# DigitalInputs.net
KiCad netlist of a schematic drawn in Altium Designer
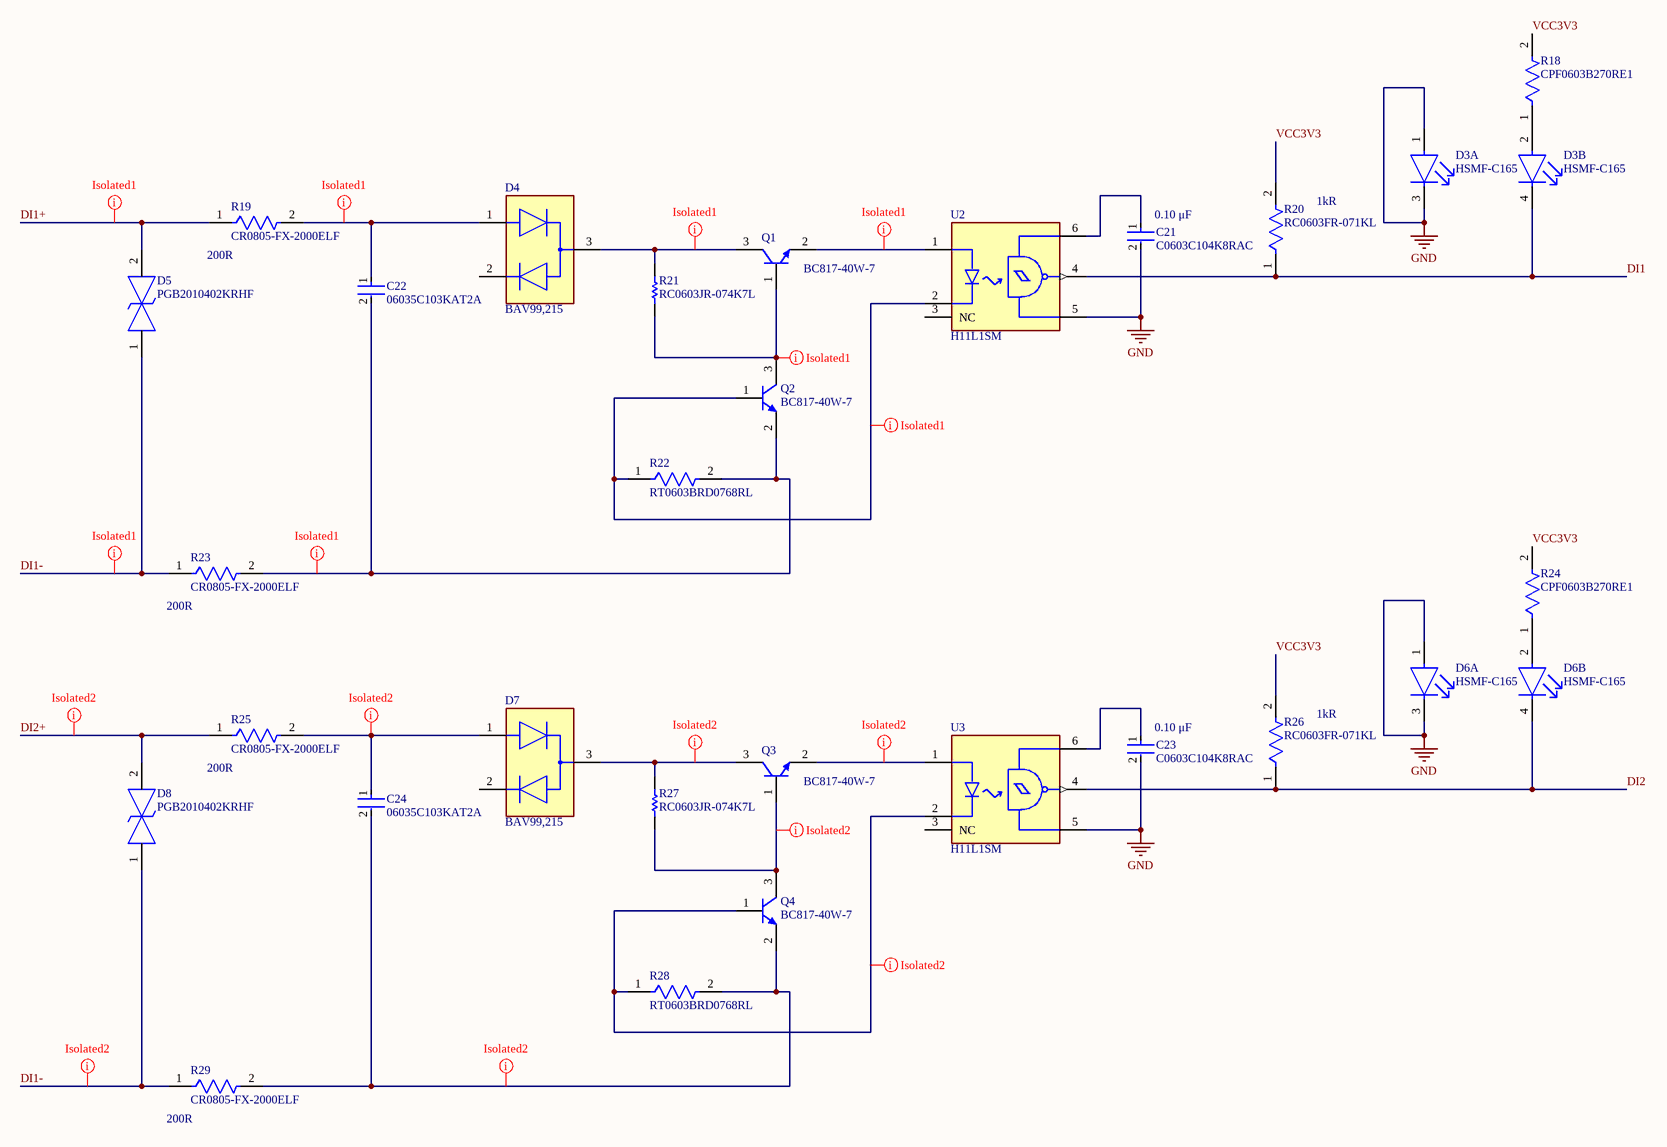
[diagram p0: DigitalInputs.SchDoc]

(export (version "E")
  (design (tool "Eeschema 10.0.6"))
  (components
    (comp (ref "C21")
      (value "C0603C104K8RAC")
      (footprint "FP-C0603C-CF-MFG")
      (description "C0603 0.10 μF X7R 30ppm/°C 10.00% 10 V")
      (fields
        (field (name "MANUFACTURER") "KEMET")
        (field (name "CAPACITANCE") "0.10 μF")
        (field (name "OCTOPART") "https://octopart.com/c0603c104k8rac-kemet-1325403")
      )
      (libsource (lib "Altium Content Vault") (part "b4654b650e69147ec39a6b967a45e02"))
    )
    (comp (ref "C22")
      (value "06035C103KAT2A")
      (footprint "FP-0603-L_1_6_0_15-W_0_81-MFG")
      (description "General Purpose Ceramic Capacitor, 0603, 10nF, 10%, X7R, 15%, 50V")
      (fields (field (name "VOLTAGE") "50V") (field (name "TOLERANCE") "10%"))
      (libsource (lib "Altium Content Vault") (part "02cd4be3c70576c341d710602a673aa"))
    )
    (comp (ref "C23")
      (value "C0603C104K8RAC")
      (footprint "FP-C0603C-CF-MFG")
      (description "C0603 0.10 μF X7R 30ppm/°C 10.00% 10 V")
      (fields
        (field (name "MANUFACTURER") "KEMET")
        (field (name "CAPACITANCE") "0.10 μF")
        (field (name "OCTOPART") "https://octopart.com/c0603c104k8rac-kemet-1325403")
      )
      (libsource (lib "Altium Content Vault") (part "b4654b650e69147ec39a6b967a45e02"))
    )
    (comp (ref "C24")
      (value "06035C103KAT2A")
      (footprint "FP-0603-L_1_6_0_15-W_0_81-MFG")
      (description "General Purpose Ceramic Capacitor, 0603, 10nF, 10%, X7R, 15%, 50V")
      (fields (field (name "VOLTAGE") "50V") (field (name "TOLERANCE") "10%"))
      (libsource (lib "Altium Content Vault") (part "02cd4be3c70576c341d710602a673aa"))
    )
    (comp (ref "D3")
      (value "HSMF-C165")
      (footprint "FP-HSMF-C165-MFG")
      (description "LED GREEN/RED DIFFUSED 0603 SMD")
      (libsource (lib "Altium Content Vault") (part "7c1fe340d8ce6b5db8c50b7ec3493de"))
    )
    (comp (ref "D4")
      (value "BAV99,215")
      (footprint "FP-SOT23-MFG")
      (description "DIODE ARRAY GP 100V 215MA SOT23")
      (libsource (lib "Altium Content Vault") (part "86a7eb6839269cc1691df5cbdd99f75"))
    )
    (comp (ref "D5")
      (value "PGB2010402KRHF")
      (footprint "DIONC1005X38N")
      (description "Littelfuse PGB2 Series Metal Oxide Varistor 0.07pF, Clamping 40V 0402 (1005M) Case")
      (fields (field (name "MOUSER PART NUMBER") "576-PGB2010402KRHF"))
      (libsource (lib "Schlib2") (part "PGB2010402KRHF"))
    )
    (comp (ref "D6")
      (value "HSMF-C165")
      (footprint "FP-HSMF-C165-MFG")
      (description "LED GREEN/RED DIFFUSED 0603 SMD")
      (libsource (lib "Altium Content Vault") (part "7c1fe340d8ce6b5db8c50b7ec3493de"))
    )
    (comp (ref "D7")
      (value "BAV99,215")
      (footprint "FP-SOT23-MFG")
      (description "DIODE ARRAY GP 100V 215MA SOT23")
      (libsource (lib "Altium Content Vault") (part "86a7eb6839269cc1691df5cbdd99f75"))
    )
    (comp (ref "D8")
      (value "PGB2010402KRHF")
      (footprint "DIONC1005X38N")
      (description "Littelfuse PGB2 Series Metal Oxide Varistor 0.07pF, Clamping 40V 0402 (1005M) Case")
      (fields (field (name "MOUSER PART NUMBER") "576-PGB2010402KRHF"))
      (libsource (lib "Schlib2") (part "PGB2010402KRHF"))
    )
    (comp (ref "Q1")
      (value "BC817-40W-7")
      (footprint "DIOD-SOT323-3_V")
      (description "NPN Small Signal Transistor, 45 V, 500 mA, -65 to 150 degC, 3-Pin SOT323, RoHS, Tape and Reel")
      (fields (field (name "MANUFACTURER") "DiodesIncorporated"))
      (libsource (lib "Altium Content Vault") (part "BJT-NPN-BEC-3"))
    )
    (comp (ref "Q2")
      (value "BC817-40W-7")
      (footprint "DIOD-SOT323-3_V")
      (description "NPN Small Signal Transistor, 45 V, 500 mA, -65 to 150 degC, 3-Pin SOT323, RoHS, Tape and Reel")
      (fields (field (name "MANUFACTURER") "DiodesIncorporated"))
      (libsource (lib "Altium Content Vault") (part "BJT-NPN-BEC-3"))
    )
    (comp (ref "Q3")
      (value "BC817-40W-7")
      (footprint "DIOD-SOT323-3_V")
      (description "NPN Small Signal Transistor, 45 V, 500 mA, -65 to 150 degC, 3-Pin SOT323, RoHS, Tape and Reel")
      (fields (field (name "MANUFACTURER") "DiodesIncorporated"))
      (libsource (lib "Altium Content Vault") (part "BJT-NPN-BEC-3"))
    )
    (comp (ref "Q4")
      (value "BC817-40W-7")
      (footprint "DIOD-SOT323-3_V")
      (description "NPN Small Signal Transistor, 45 V, 500 mA, -65 to 150 degC, 3-Pin SOT323, RoHS, Tape and Reel")
      (fields (field (name "MANUFACTURER") "DiodesIncorporated"))
      (libsource (lib "Altium Content Vault") (part "BJT-NPN-BEC-3"))
    )
    (comp (ref "R18")
      (value "CPF0603B270RE1")
      (footprint "FP-CPF0603-MFG")
      (description "RES SMD 270Ω 0.1% 1/16W 0603")
      (fields (field (name "TOLERANCE") "0.1%") (field (name "MANUFACTURER") "TE Connectivity"))
      (libsource (lib "Altium Content Vault") (part "1029c3af85768c4190bb7ad29bc67b5"))
    )
    (comp (ref "R19")
      (value "CR0805-FX-2000ELF")
      (footprint "FP-CR0805-IPC_B")
      (description "Thick Film Chip Resistors 0805 200Ω 0.125W 1% 100ppm/°C")
      (fields (field (name "TOLERANCE") "1%") (field (name "RESISTANCE") "200R"))
      (libsource (lib "Altium Content Vault") (part "1029c3af85768c4190bb7ad29bc67b5"))
    )
    (comp (ref "R20")
      (value "RC0603FR-071KL")
      (footprint "FP-RC0603-0_55-IPC_C")
      (description "RES 1K OHM 1% 1/10W 0603")
      (fields (field (name "RESISTANCE") "1kR") (field (name "TOLERANCE") "1%"))
      (libsource (lib "Altium Content Vault") (part "1029c3af85768c4190bb7ad29bc67b5"))
    )
    (comp (ref "R21")
      (value "RC0603JR-074K7L")
      (footprint "RESC1608X55X25ML10T15")
      (description "Chip Resistor, 4.7 KOhm, +/- 5%, 100 mW, -55 to 155 degC, 0603 (1608 Metric), RoHS, Tape and Reel")
      (fields (field (name "TOLERANCE") "5%") (field (name "MANUFACTURER") "Yageo"))
      (libsource (lib "Altium Content Vault") (part "RES-2"))
    )
    (comp (ref "R22")
      (value "RT0603BRD0768RL")
      (footprint "FP-RT0603-MFG")
      (description "RES 68.0 OHM 1/10W .1% SMD 0603")
      (fields
        (field (name "MANUFACTURER") "Yageo")
        (field (name "OCTOPART") "https://octopart.com/rt0603brd0768rl-yageo-1442936")
      )
      (libsource (lib "Altium Content Vault") (part "1029c3af85768c4190bb7ad29bc67b5"))
    )
    (comp (ref "R23")
      (value "CR0805-FX-2000ELF")
      (footprint "FP-CR0805-IPC_B")
      (description "Thick Film Chip Resistors 0805 200Ω 0.125W 1% 100ppm/°C")
      (fields (field (name "TOLERANCE") "1%") (field (name "RESISTANCE") "200R"))
      (libsource (lib "Altium Content Vault") (part "1029c3af85768c4190bb7ad29bc67b5"))
    )
    (comp (ref "R24")
      (value "CPF0603B270RE1")
      (footprint "FP-CPF0603-MFG")
      (description "RES SMD 270Ω 0.1% 1/16W 0603")
      (fields (field (name "TOLERANCE") "0.1%") (field (name "MANUFACTURER") "TE Connectivity"))
      (libsource (lib "Altium Content Vault") (part "1029c3af85768c4190bb7ad29bc67b5"))
    )
    (comp (ref "R25")
      (value "CR0805-FX-2000ELF")
      (footprint "FP-CR0805-IPC_B")
      (description "Thick Film Chip Resistors 0805 200Ω 0.125W 1% 100ppm/°C")
      (fields (field (name "TOLERANCE") "1%") (field (name "RESISTANCE") "200R"))
      (libsource (lib "Altium Content Vault") (part "1029c3af85768c4190bb7ad29bc67b5"))
    )
    (comp (ref "R26")
      (value "RC0603FR-071KL")
      (footprint "FP-RC0603-0_55-IPC_C")
      (description "RES 1K OHM 1% 1/10W 0603")
      (fields (field (name "RESISTANCE") "1kR") (field (name "TOLERANCE") "1%"))
      (libsource (lib "Altium Content Vault") (part "1029c3af85768c4190bb7ad29bc67b5"))
    )
    (comp (ref "R27")
      (value "RC0603JR-074K7L")
      (footprint "RESC1608X55X25ML10T15")
      (description "Chip Resistor, 4.7 KOhm, +/- 5%, 100 mW, -55 to 155 degC, 0603 (1608 Metric), RoHS, Tape and Reel")
      (fields (field (name "TOLERANCE") "5%") (field (name "MANUFACTURER") "Yageo"))
      (libsource (lib "Altium Content Vault") (part "RES-2"))
    )
    (comp (ref "R28")
      (value "RT0603BRD0768RL")
      (footprint "FP-RT0603-MFG")
      (description "RES 68.0 OHM 1/10W .1% SMD 0603")
      (fields
        (field (name "MANUFACTURER") "Yageo")
        (field (name "OCTOPART") "https://octopart.com/rt0603brd0768rl-yageo-1442936")
      )
      (libsource (lib "Altium Content Vault") (part "1029c3af85768c4190bb7ad29bc67b5"))
    )
    (comp (ref "R29")
      (value "CR0805-FX-2000ELF")
      (footprint "FP-CR0805-IPC_B")
      (description "Thick Film Chip Resistors 0805 200Ω 0.125W 1% 100ppm/°C")
      (fields (field (name "TOLERANCE") "1%") (field (name "RESISTANCE") "200R"))
      (libsource (lib "Altium Content Vault") (part "1029c3af85768c4190bb7ad29bc67b5"))
    )
    (comp (ref "U2")
      (value "H11L1SM")
      (footprint "FP-646BY-MFG")
      (description "OPTOISO 4.17KV OPN COLL 6SMD")
      (fields
        (field (name "MANUFACTURER") "ON Semiconductor")
        (field (name "OCTOPART") "https://octopart.com/h11l1sm-on+semiconductor-84328916")
      )
      (libsource (lib "Altium Content Vault") (part "e3909e1d209c9787f54f3dc2cca47f5"))
    )
    (comp (ref "U3")
      (value "H11L1SM")
      (footprint "FP-646BY-MFG")
      (description "OPTOISO 4.17KV OPN COLL 6SMD")
      (fields
        (field (name "MANUFACTURER") "ON Semiconductor")
        (field (name "OCTOPART") "https://octopart.com/h11l1sm-on+semiconductor-84328916")
      )
      (libsource (lib "Altium Content Vault") (part "e3909e1d209c9787f54f3dc2cca47f5"))
    )
  )
  (nets
    (net (code "1") (name "/DI1") (class "Default")
      (node (ref "D3") (pin "4") (pinfunction "RED_C_4") (pintype "passive"))
      (node (ref "R20") (pin "1") (pinfunction "1_1") (pintype "passive"))
      (node (ref "U2") (pin "4") (pinfunction "VO_4") (pintype "output"))
    )
    (net (code "2") (name "/DI1+") (class "Default")
      (node (ref "D5") (pin "2") (pinfunction "2_2") (pintype "passive"))
      (node (ref "R19") (pin "1") (pinfunction "1_1") (pintype "passive"))
    )
    (net (code "3") (name "/DI1-") (class "Default")
      (node (ref "D5") (pin "1") (pinfunction "1_1") (pintype "passive"))
      (node (ref "D8") (pin "1") (pinfunction "1_1") (pintype "passive"))
      (node (ref "R23") (pin "1") (pinfunction "1_1") (pintype "passive"))
      (node (ref "R29") (pin "1") (pinfunction "1_1") (pintype "passive"))
    )
    (net (code "4") (name "/DI2") (class "Default")
      (node (ref "D6") (pin "4") (pinfunction "RED_C_4") (pintype "passive"))
      (node (ref "R26") (pin "1") (pinfunction "1_1") (pintype "passive"))
      (node (ref "U3") (pin "4") (pinfunction "VO_4") (pintype "output"))
    )
    (net (code "5") (name "/DI2+") (class "Default")
      (node (ref "D8") (pin "2") (pinfunction "2_2") (pintype "passive"))
      (node (ref "R25") (pin "1") (pinfunction "1_1") (pintype "passive"))
    )
    (net (code "6") (name "/VCC3V3") (class "Default")
      (node (ref "R18") (pin "2") (pinfunction "2_2") (pintype "passive"))
      (node (ref "R20") (pin "2") (pinfunction "2_2") (pintype "passive"))
      (node (ref "R24") (pin "2") (pinfunction "2_2") (pintype "passive"))
      (node (ref "R26") (pin "2") (pinfunction "2_2") (pintype "passive"))
    )
    (net (code "7") (name "GND") (class "Default")
      (node (ref "C21") (pin "2") (pinfunction "2_2") (pintype "passive"))
      (node (ref "C23") (pin "2") (pinfunction "2_2") (pintype "passive"))
      (node (ref "D3") (pin "1") (pinfunction "GREEN_A_1") (pintype "passive"))
      (node (ref "D3") (pin "3") (pinfunction "GREEN_C_3") (pintype "passive"))
      (node (ref "D6") (pin "1") (pinfunction "GREEN_A_1") (pintype "passive"))
      (node (ref "D6") (pin "3") (pinfunction "GREEN_C_3") (pintype "passive"))
      (node (ref "U2") (pin "5") (pinfunction "GND_5") (pintype "power_in"))
      (node (ref "U3") (pin "5") (pinfunction "GND_5") (pintype "power_in"))
    )
    (net (code "8") (name "Net-(C22-Pad1)") (class "Default")
      (node (ref "C22") (pin "1") (pinfunction "1_1") (pintype "passive"))
      (node (ref "D4") (pin "1") (pinfunction "1_1") (pintype "passive"))
      (node (ref "R19") (pin "2") (pinfunction "2_2") (pintype "passive"))
    )
    (net (code "9") (name "Net-(C24-Pad1)") (class "Default")
      (node (ref "C24") (pin "1") (pinfunction "1_1") (pintype "passive"))
      (node (ref "D7") (pin "1") (pinfunction "1_1") (pintype "passive"))
      (node (ref "R25") (pin "2") (pinfunction "2_2") (pintype "passive"))
    )
    (net (code "10") (name "Net-(D3B-RED_A)") (class "Default")
      (node (ref "D3") (pin "2") (pinfunction "RED_A_2") (pintype "passive"))
      (node (ref "R18") (pin "1") (pinfunction "1_1") (pintype "passive"))
    )
    (net (code "11") (name "Net-(D6B-RED_A)") (class "Default")
      (node (ref "D6") (pin "2") (pinfunction "RED_A_2") (pintype "passive"))
      (node (ref "R24") (pin "1") (pinfunction "1_1") (pintype "passive"))
    )
    (net (code "12") (name "Net-(Q1-B)") (class "Default")
      (node (ref "Q1") (pin "1") (pinfunction "B_1") (pintype "passive"))
      (node (ref "Q2") (pin "3") (pinfunction "C_3") (pintype "passive"))
      (node (ref "R21") (pin "1") (pinfunction "1_1") (pintype "passive"))
    )
    (net (code "13") (name "Net-(Q1-C)") (class "Default")
      (node (ref "D4") (pin "3") (pinfunction "3_3") (pintype "passive"))
      (node (ref "Q1") (pin "3") (pinfunction "C_3") (pintype "passive"))
      (node (ref "R21") (pin "2") (pinfunction "2_2") (pintype "passive"))
    )
    (net (code "14") (name "Net-(Q1-E)") (class "Default")
      (node (ref "Q1") (pin "2") (pinfunction "E_2") (pintype "passive"))
      (node (ref "U2") (pin "1") (pinfunction "A_1") (pintype "passive"))
    )
    (net (code "15") (name "Net-(Q2-B)") (class "Default")
      (node (ref "Q2") (pin "1") (pinfunction "B_1") (pintype "passive"))
      (node (ref "R22") (pin "1") (pinfunction "1_1") (pintype "passive"))
      (node (ref "U2") (pin "2") (pinfunction "C_2") (pintype "passive"))
    )
    (net (code "16") (name "Net-(Q2-E)") (class "Default")
      (node (ref "C22") (pin "2") (pinfunction "2_2") (pintype "passive"))
      (node (ref "Q2") (pin "2") (pinfunction "E_2") (pintype "passive"))
      (node (ref "R22") (pin "2") (pinfunction "2_2") (pintype "passive"))
      (node (ref "R23") (pin "2") (pinfunction "2_2") (pintype "passive"))
    )
    (net (code "17") (name "Net-(Q3-B)") (class "Default")
      (node (ref "Q3") (pin "1") (pinfunction "B_1") (pintype "passive"))
      (node (ref "Q4") (pin "3") (pinfunction "C_3") (pintype "passive"))
      (node (ref "R27") (pin "1") (pinfunction "1_1") (pintype "passive"))
    )
    (net (code "18") (name "Net-(Q3-C)") (class "Default")
      (node (ref "D7") (pin "3") (pinfunction "3_3") (pintype "passive"))
      (node (ref "Q3") (pin "3") (pinfunction "C_3") (pintype "passive"))
      (node (ref "R27") (pin "2") (pinfunction "2_2") (pintype "passive"))
    )
    (net (code "19") (name "Net-(Q3-E)") (class "Default")
      (node (ref "Q3") (pin "2") (pinfunction "E_2") (pintype "passive"))
      (node (ref "U3") (pin "1") (pinfunction "A_1") (pintype "passive"))
    )
    (net (code "20") (name "Net-(Q4-B)") (class "Default")
      (node (ref "Q4") (pin "1") (pinfunction "B_1") (pintype "passive"))
      (node (ref "R28") (pin "1") (pinfunction "1_1") (pintype "passive"))
      (node (ref "U3") (pin "2") (pinfunction "C_2") (pintype "passive"))
    )
    (net (code "21") (name "Net-(Q4-E)") (class "Default")
      (node (ref "C24") (pin "2") (pinfunction "2_2") (pintype "passive"))
      (node (ref "Q4") (pin "2") (pinfunction "E_2") (pintype "passive"))
      (node (ref "R28") (pin "2") (pinfunction "2_2") (pintype "passive"))
      (node (ref "R29") (pin "2") (pinfunction "2_2") (pintype "passive"))
    )
    (net (code "22") (name "Net-(U2-VCC)") (class "Default")
      (node (ref "C21") (pin "1") (pinfunction "1_1") (pintype "passive"))
      (node (ref "U2") (pin "6") (pinfunction "VCC_6") (pintype "power_in"))
    )
    (net (code "23") (name "Net-(U3-VCC)") (class "Default")
      (node (ref "C23") (pin "1") (pinfunction "1_1") (pintype "passive"))
      (node (ref "U3") (pin "6") (pinfunction "VCC_6") (pintype "power_in"))
    )
    (net (code "24") (name "unconnected-(D4-Pad2)") (class "Default")
      (node (ref "D4") (pin "2") (pinfunction "2_2") (pintype "passive"))
    )
    (net (code "25") (name "unconnected-(D7-Pad2)") (class "Default")
      (node (ref "D7") (pin "2") (pinfunction "2_2") (pintype "passive"))
    )
    (net (code "26") (name "unconnected-(U2-NC-Pad3)") (class "Default")
      (node (ref "U2") (pin "3") (pinfunction "NC_3") (pintype "passive"))
    )
    (net (code "27") (name "unconnected-(U3-NC-Pad3)") (class "Default")
      (node (ref "U3") (pin "3") (pinfunction "NC_3") (pintype "passive"))
    )
  )
)
